# PCB_CoLAB_Schematic_V2.net
KiCad netlist of a schematic drawn in EAGLE
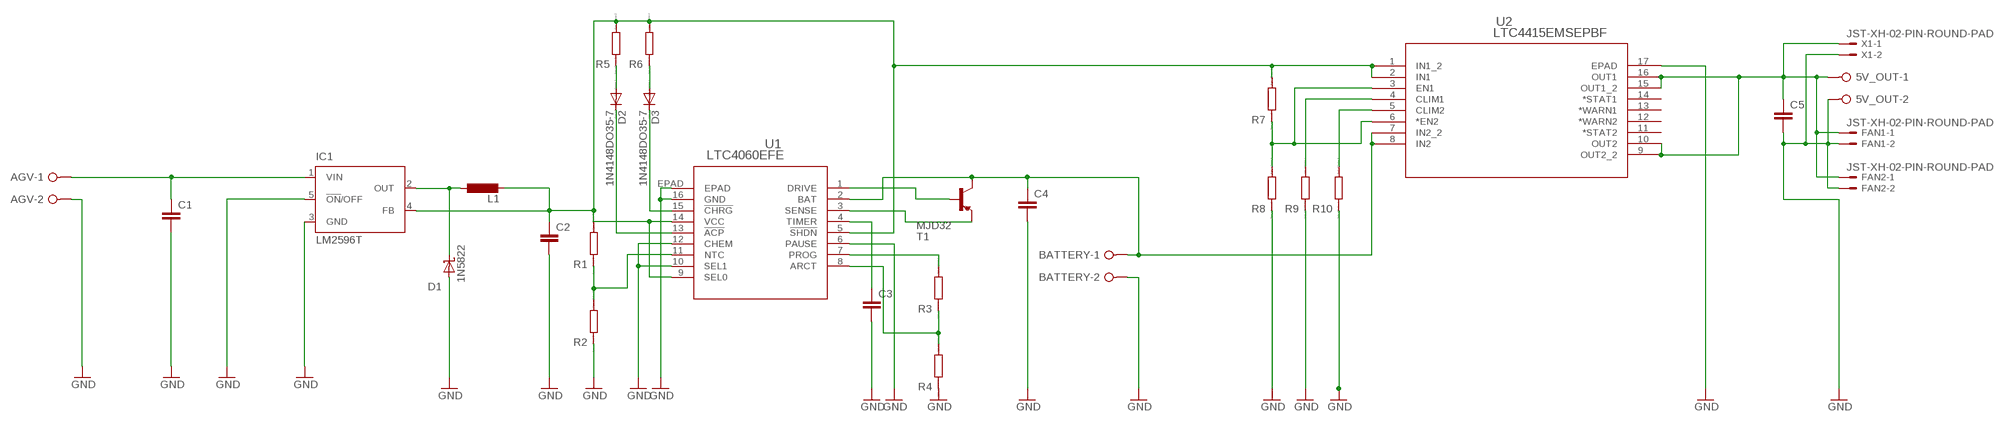
[diagram p0: schematic, sheet 1]

(export (version "E")
  (design (tool "Eeschema 10.0.6"))
  (components
    (comp (ref "5V_OUT")
      (value "W237-02P")
      (footprint "eagle-import:W237-132")
      (libsource (lib "eagle-import") (part "W237-02P"))
    )
    (comp (ref "AGV")
      (value "W237-02P")
      (footprint "eagle-import:W237-132")
      (libsource (lib "eagle-import") (part "W237-02P"))
    )
    (comp (ref "BATTERY")
      (value "W237-02P")
      (footprint "eagle-import:W237-132")
      (libsource (lib "eagle-import") (part "W237-02P"))
    )
    (comp (ref "C1")
      (value "C-EU025-024X044")
      (footprint "eagle-import:C025-024X044")
      (libsource (lib "eagle-import") (part "C-EU025-024X044"))
    )
    (comp (ref "C2")
      (value "C-EU025-024X044")
      (footprint "eagle-import:C025-024X044")
      (libsource (lib "eagle-import") (part "C-EU025-024X044"))
    )
    (comp (ref "C3")
      (value "C-EU025-024X044")
      (footprint "eagle-import:C025-024X044")
      (libsource (lib "eagle-import") (part "C-EU025-024X044"))
    )
    (comp (ref "C4")
      (value "C-EU025-024X044")
      (footprint "eagle-import:C025-024X044")
      (libsource (lib "eagle-import") (part "C-EU025-024X044"))
    )
    (comp (ref "C5")
      (value "C-EU025-024X044")
      (footprint "eagle-import:C025-024X044")
      (libsource (lib "eagle-import") (part "C-EU025-024X044"))
    )
    (comp (ref "D1")
      (value "1N5822")
      (footprint "eagle-import:DIOAD2120W130L950D530P")
      (fields (field (name "MF") "ON Semiconductor"))
      (libsource (lib "eagle-import") (part "1N5822"))
    )
    (comp (ref "D2")
      (value "1N4148DO35-7")
      (footprint "eagle-import:DO35-7")
      (libsource (lib "eagle-import") (part "1N4148DO35-7"))
    )
    (comp (ref "D3")
      (value "1N4148DO35-7")
      (footprint "eagle-import:DO35-7")
      (libsource (lib "eagle-import") (part "1N4148DO35-7"))
    )
    (comp (ref "FAN1")
      (value "JST-XH-02-PIN-ROUND-PAD")
      (footprint "eagle-import:JST-XH-02-PACKAGE-ROUND-PAD")
      (libsource (lib "eagle-import") (part "JST-XH-02-PIN-ROUND-PAD"))
    )
    (comp (ref "FAN2")
      (value "JST-XH-02-PIN-ROUND-PAD")
      (footprint "eagle-import:JST-XH-02-PACKAGE-ROUND-PAD")
      (libsource (lib "eagle-import") (part "JST-XH-02-PIN-ROUND-PAD"))
    )
    (comp (ref "IC1")
      (value "LM2596T")
      (footprint "eagle-import:T05D")
      (fields (field (name "MPN") "LM2596T-ADJ/LF02"))
      (libsource (lib "eagle-import") (part "LM2596T"))
    )
    (comp (ref "L1")
      (value "L-EU0204/7")
      (footprint "eagle-import:0204_7")
      (libsource (lib "eagle-import") (part "L-EU0204/7"))
    )
    (comp (ref "R1")
      (value "R0204/7")
      (footprint "eagle-import:0204_7")
      (libsource (lib "eagle-import") (part "R0204/7"))
    )
    (comp (ref "R2")
      (value "R0204/7")
      (footprint "eagle-import:0204_7")
      (libsource (lib "eagle-import") (part "R0204/7"))
    )
    (comp (ref "R3")
      (value "R0204/7")
      (footprint "eagle-import:0204_7")
      (libsource (lib "eagle-import") (part "R0204/7"))
    )
    (comp (ref "R4")
      (value "R0204/7")
      (footprint "eagle-import:0204_7")
      (libsource (lib "eagle-import") (part "R0204/7"))
    )
    (comp (ref "R5")
      (value "R0204/7")
      (footprint "eagle-import:0204_7")
      (libsource (lib "eagle-import") (part "R0204/7"))
    )
    (comp (ref "R6")
      (value "R0204/7")
      (footprint "eagle-import:0204_7")
      (libsource (lib "eagle-import") (part "R0204/7"))
    )
    (comp (ref "R7")
      (value "R0204/7")
      (footprint "eagle-import:0204_7")
      (libsource (lib "eagle-import") (part "R0204/7"))
    )
    (comp (ref "R8")
      (value "R0204/7")
      (footprint "eagle-import:0204_7")
      (libsource (lib "eagle-import") (part "R0204/7"))
    )
    (comp (ref "R9")
      (value "R0204/7")
      (footprint "eagle-import:0204_7")
      (libsource (lib "eagle-import") (part "R0204/7"))
    )
    (comp (ref "R10")
      (value "R0204/7")
      (footprint "eagle-import:0204_7")
      (libsource (lib "eagle-import") (part "R0204/7"))
    )
    (comp (ref "T1")
      (value "MJD32")
      (footprint "eagle-import:DPAK")
      (libsource (lib "eagle-import") (part "MJD32"))
    )
    (comp (ref "U1")
      (value "LTC4060EFE")
      (footprint "eagle-import:TSSOP-16_FE_BC_LIT")
      (libsource (lib "eagle-import") (part "LTC4060EFE"))
    )
    (comp (ref "U2")
      (value "LTC4415EMSEPBF")
      (footprint "eagle-import:MSOP-16_MSE")
      (fields (field (name "MF") "Analog Devices") (field (name "MP") "LTC4415EMSE#PBF"))
      (libsource (lib "eagle-import") (part "LTC4415EMSEPBF"))
    )
    (comp (ref "X1")
      (value "JST-XH-02-PIN-ROUND-PAD")
      (footprint "eagle-import:JST-XH-02-PACKAGE-ROUND-PAD")
      (libsource (lib "eagle-import") (part "JST-XH-02-PIN-ROUND-PAD"))
    )
  )
  (nets
    (net (code "1") (name "GND") (class "Default")
      (node (ref "5V_OUT") (pin "2") (pinfunction "KL_2") (pintype "passive"))
      (node (ref "AGV") (pin "2") (pinfunction "KL_2") (pintype "passive"))
      (node (ref "BATTERY") (pin "2") (pinfunction "KL_2") (pintype "passive"))
      (node (ref "C1") (pin "2") (pinfunction "2_2") (pintype "passive"))
      (node (ref "C2") (pin "2") (pinfunction "2_2") (pintype "passive"))
      (node (ref "C3") (pin "2") (pinfunction "2_2") (pintype "passive"))
      (node (ref "C4") (pin "2") (pinfunction "2_2") (pintype "passive"))
      (node (ref "C5") (pin "2") (pinfunction "2_2") (pintype "passive"))
      (node (ref "D1") (pin "A") (pinfunction "A_A") (pintype "passive"))
      (node (ref "FAN1") (pin "2") (pinfunction "S_2") (pintype "passive"))
      (node (ref "FAN2") (pin "2") (pinfunction "S_2") (pintype "passive"))
      (node (ref "IC1") (pin "3") (pinfunction "GND_3") (pintype "power_in"))
      (node (ref "IC1") (pin "5") (pinfunction "~{ON}/OFF_5") (pintype "input"))
      (node (ref "R10") (pin "1") (pinfunction "1_1") (pintype "passive"))
      (node (ref "R2") (pin "1") (pinfunction "1_1") (pintype "passive"))
      (node (ref "R4") (pin "1") (pinfunction "1_1") (pintype "passive"))
      (node (ref "R8") (pin "1") (pinfunction "1_1") (pintype "passive"))
      (node (ref "R9") (pin "1") (pinfunction "1_1") (pintype "passive"))
      (node (ref "U1") (pin "10") (pinfunction "SEL1_10") (pintype "input"))
      (node (ref "U1") (pin "12") (pinfunction "CHEM_12") (pintype "input"))
      (node (ref "U1") (pin "16") (pinfunction "GND_16") (pintype "power_in"))
      (node (ref "U1") (pin "6") (pinfunction "PAUSE_6") (pintype "input"))
      (node (ref "U1") (pin "EPAD") (pinfunction "EPAD_EPAD") (pintype "passive"))
      (node (ref "U2") (pin "17") (pinfunction "EPAD_17") (pintype "passive"))
      (node (ref "X1") (pin "2") (pinfunction "S_2") (pintype "passive"))
    )
    (net (code "2") (name "Net-(5V_OUTA-KL)") (class "Default")
      (node (ref "5V_OUT") (pin "1") (pinfunction "KL_1") (pintype "passive"))
      (node (ref "C5") (pin "1") (pinfunction "1_1") (pintype "passive"))
      (node (ref "FAN1") (pin "1") (pinfunction "S_1") (pintype "passive"))
      (node (ref "FAN2") (pin "1") (pinfunction "S_1") (pintype "passive"))
      (node (ref "U2") (pin "10") (pinfunction "OUT2_10") (pintype "output"))
      (node (ref "U2") (pin "15") (pinfunction "OUT1_2_15") (pintype "output"))
      (node (ref "U2") (pin "16") (pinfunction "OUT1_16") (pintype "output"))
      (node (ref "U2") (pin "9") (pinfunction "OUT2_2_9") (pintype "output"))
      (node (ref "X1") (pin "1") (pinfunction "S_1") (pintype "passive"))
    )
    (net (code "3") (name "Net-(AGVA-KL)") (class "Default")
      (node (ref "AGV") (pin "1") (pinfunction "KL_1") (pintype "passive"))
      (node (ref "C1") (pin "1") (pinfunction "1_1") (pintype "passive"))
      (node (ref "IC1") (pin "1") (pinfunction "VIN_1") (pintype "input"))
    )
    (net (code "4") (name "Net-(BATTERYA-KL)") (class "Default")
      (node (ref "BATTERY") (pin "1") (pinfunction "KL_1") (pintype "passive"))
      (node (ref "C4") (pin "1") (pinfunction "1_1") (pintype "passive"))
      (node (ref "T1") (pin "4") (pinfunction "C_4") (pintype "passive"))
      (node (ref "U1") (pin "2") (pinfunction "BAT_2") (pintype "input"))
      (node (ref "U2") (pin "7") (pinfunction "IN2_2_7") (pintype "input"))
      (node (ref "U2") (pin "8") (pinfunction "IN2_8") (pintype "input"))
    )
    (net (code "5") (name "Net-(D2-PadA)") (class "Default")
      (node (ref "D2") (pin "A") (pinfunction "A_A") (pintype "passive"))
      (node (ref "R5") (pin "1") (pinfunction "1_1") (pintype "passive"))
    )
    (net (code "6") (name "Net-(D3-PadA)") (class "Default")
      (node (ref "D3") (pin "A") (pinfunction "A_A") (pintype "passive"))
      (node (ref "R6") (pin "1") (pinfunction "1_1") (pintype "passive"))
    )
    (net (code "7") (name "Net-(IC1-FB)") (class "Default")
      (node (ref "C2") (pin "1") (pinfunction "1_1") (pintype "passive"))
      (node (ref "IC1") (pin "4") (pinfunction "FB_4") (pintype "input"))
      (node (ref "L1") (pin "2") (pinfunction "2_2") (pintype "passive"))
      (node (ref "R1") (pin "2") (pinfunction "2_2") (pintype "passive"))
      (node (ref "R5") (pin "2") (pinfunction "2_2") (pintype "passive"))
      (node (ref "R6") (pin "2") (pinfunction "2_2") (pintype "passive"))
      (node (ref "R7") (pin "2") (pinfunction "2_2") (pintype "passive"))
      (node (ref "U1") (pin "14") (pinfunction "VCC_14") (pintype "power_in"))
      (node (ref "U1") (pin "5") (pinfunction "~{SHDN}_5") (pintype "input"))
      (node (ref "U1") (pin "9") (pinfunction "SEL0_9") (pintype "input"))
      (node (ref "U2") (pin "1") (pinfunction "IN1_2_1") (pintype "input"))
      (node (ref "U2") (pin "2") (pinfunction "IN1_2") (pintype "input"))
    )
    (net (code "8") (name "Net-(IC1-OUT)") (class "Default")
      (node (ref "D1") (pin "C") (pinfunction "C_C") (pintype "passive"))
      (node (ref "IC1") (pin "2") (pinfunction "OUT_2") (pintype "output"))
      (node (ref "L1") (pin "1") (pinfunction "1_1") (pintype "passive"))
    )
    (net (code "9") (name "Net-(T1-B)") (class "Default")
      (node (ref "T1") (pin "1") (pinfunction "B_1") (pintype "passive"))
      (node (ref "U1") (pin "1") (pinfunction "DRIVE_1") (pintype "output"))
    )
    (net (code "10") (name "Net-(T1-E)") (class "Default")
      (node (ref "T1") (pin "3") (pinfunction "E_3") (pintype "passive"))
      (node (ref "U1") (pin "3") (pinfunction "SENSE_3") (pintype "input"))
    )
    (net (code "11") (name "Net-(U1-ARCT)") (class "Default")
      (node (ref "R3") (pin "1") (pinfunction "1_1") (pintype "passive"))
      (node (ref "R4") (pin "2") (pinfunction "2_2") (pintype "passive"))
      (node (ref "U1") (pin "8") (pinfunction "ARCT_8") (pintype "input"))
    )
    (net (code "12") (name "Net-(U1-NTC)") (class "Default")
      (node (ref "R1") (pin "1") (pinfunction "1_1") (pintype "passive"))
      (node (ref "R2") (pin "2") (pinfunction "2_2") (pintype "passive"))
      (node (ref "U1") (pin "11") (pinfunction "NTC_11") (pintype "input"))
    )
    (net (code "13") (name "Net-(U1-PROG)") (class "Default")
      (node (ref "R3") (pin "2") (pinfunction "2_2") (pintype "passive"))
      (node (ref "U1") (pin "7") (pinfunction "PROG_7") (pintype "input"))
    )
    (net (code "14") (name "Net-(U1-TIMER)") (class "Default")
      (node (ref "C3") (pin "1") (pinfunction "1_1") (pintype "passive"))
      (node (ref "U1") (pin "4") (pinfunction "TIMER_4") (pintype "input"))
    )
    (net (code "15") (name "Net-(U1-~{ACP})") (class "Default")
      (node (ref "D2") (pin "C") (pinfunction "C_C") (pintype "passive"))
      (node (ref "U1") (pin "13") (pinfunction "~{ACP}_13") (pintype "output"))
    )
    (net (code "16") (name "Net-(U1-~{CHRG})") (class "Default")
      (node (ref "D3") (pin "C") (pinfunction "C_C") (pintype "passive"))
      (node (ref "U1") (pin "15") (pinfunction "~{CHRG}_15") (pintype "output"))
    )
    (net (code "17") (name "Net-(U2-*EN2)") (class "Default")
      (node (ref "R7") (pin "1") (pinfunction "1_1") (pintype "passive"))
      (node (ref "R8") (pin "2") (pinfunction "2_2") (pintype "passive"))
      (node (ref "U2") (pin "3") (pinfunction "EN1_3") (pintype "input"))
      (node (ref "U2") (pin "6") (pinfunction "*EN2_6") (pintype "input"))
    )
    (net (code "18") (name "Net-(U2-CLIM1)") (class "Default")
      (node (ref "R9") (pin "2") (pinfunction "2_2") (pintype "passive"))
      (node (ref "U2") (pin "4") (pinfunction "CLIM1_4") (pintype "passive"))
    )
    (net (code "19") (name "Net-(U2-CLIM2)") (class "Default")
      (node (ref "R10") (pin "2") (pinfunction "2_2") (pintype "passive"))
      (node (ref "U2") (pin "5") (pinfunction "CLIM2_5") (pintype "passive"))
    )
    (net (code "20") (name "unconnected-(U2-*STAT1-Pad14)") (class "Default")
      (node (ref "U2") (pin "14") (pinfunction "*STAT1_14") (pintype "output"))
    )
    (net (code "21") (name "unconnected-(U2-*STAT2-Pad11)") (class "Default")
      (node (ref "U2") (pin "11") (pinfunction "*STAT2_11") (pintype "output"))
    )
    (net (code "22") (name "unconnected-(U2-*WARN1-Pad13)") (class "Default")
      (node (ref "U2") (pin "13") (pinfunction "*WARN1_13") (pintype "output"))
    )
    (net (code "23") (name "unconnected-(U2-*WARN2-Pad12)") (class "Default")
      (node (ref "U2") (pin "12") (pinfunction "*WARN2_12") (pintype "output"))
    )
  )
)
